# zigduino-micro-1.net
KiCad netlist of a schematic drawn in EAGLE
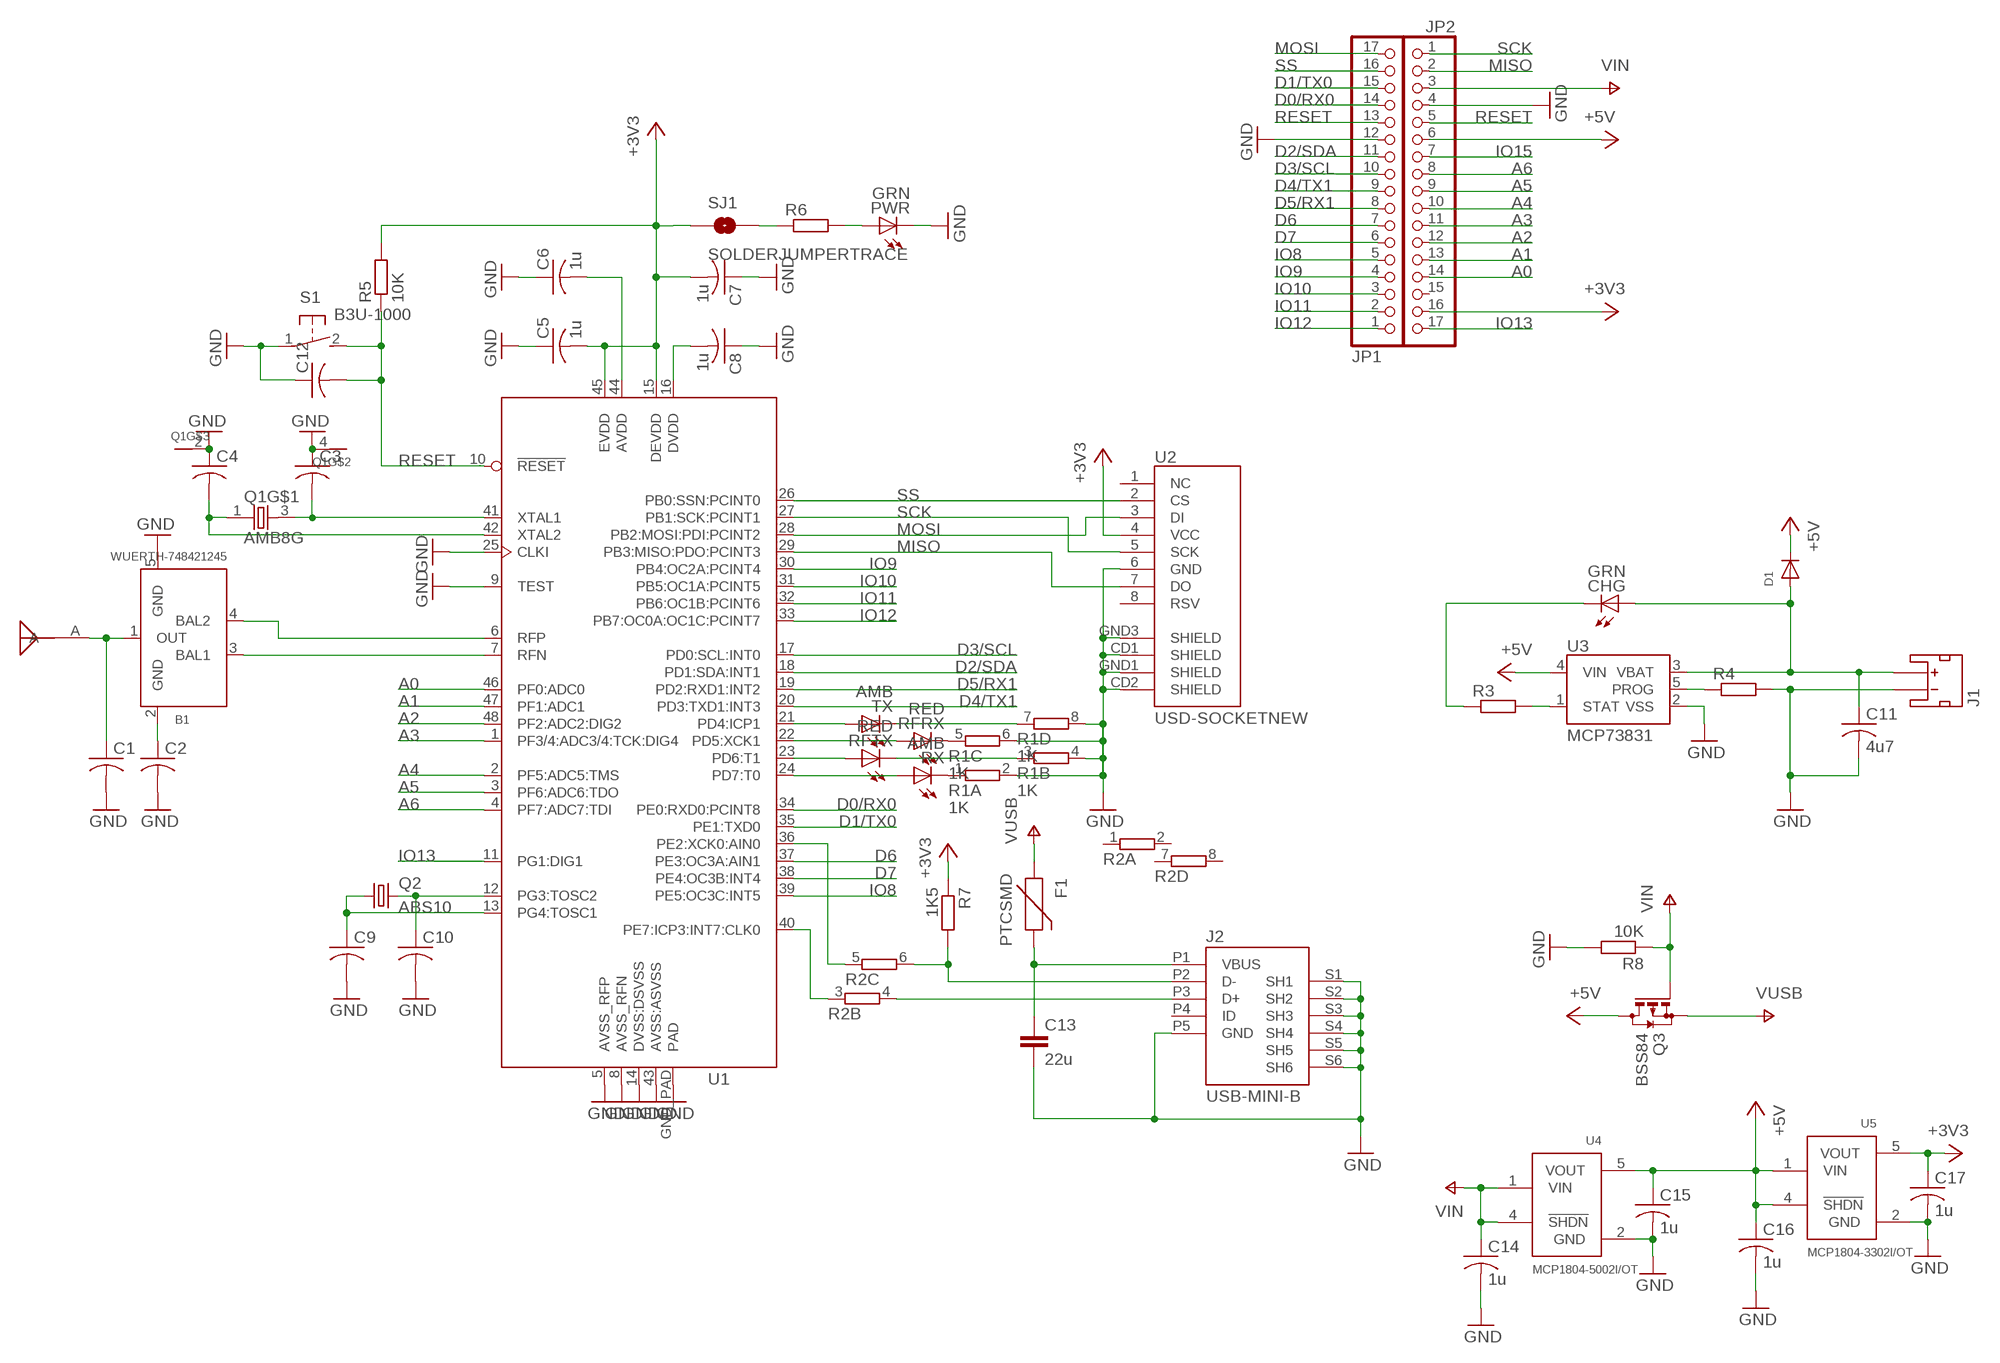
[diagram p0: schematic, sheet 1]

(export (version "E")
  (design (tool "Eeschema 10.0.6"))
  (components
    (comp (ref "ANT1")
      (value "ATMEGA128RFA1_MOLEX-ANT")
      (footprint "eagle-import:ATMEGA128RFA1_MOLEX-ANT")
      (libsource (lib "eagle-import") (part "ATMEGA128RFA1_MOLEX-ANT"))
    )
    (comp (ref "B1")
      (value "WUERTH-748421245")
      (footprint "eagle-import:WURTH-BALUN")
      (libsource (lib "eagle-import") (part "WUERTH-748421245"))
    )
    (comp (ref "C1")
      (value "C-USC0402")
      (footprint "eagle-import:C0402")
      (libsource (lib "eagle-import") (part "C-USC0402"))
    )
    (comp (ref "C2")
      (value "C-USC0402")
      (footprint "eagle-import:C0402")
      (libsource (lib "eagle-import") (part "C-USC0402"))
    )
    (comp (ref "C3")
      (value "C-USC0402")
      (footprint "eagle-import:C0402")
      (libsource (lib "eagle-import") (part "C-USC0402"))
    )
    (comp (ref "C4")
      (value "C-USC0402")
      (footprint "eagle-import:C0402")
      (libsource (lib "eagle-import") (part "C-USC0402"))
    )
    (comp (ref "C5")
      (value "1u")
      (footprint "eagle-import:C0402")
      (libsource (lib "eagle-import") (part "C-USC0402"))
    )
    (comp (ref "C6")
      (value "1u")
      (footprint "eagle-import:C0402")
      (libsource (lib "eagle-import") (part "C-USC0402"))
    )
    (comp (ref "C7")
      (value "1u")
      (footprint "eagle-import:C0402")
      (libsource (lib "eagle-import") (part "C-USC0402"))
    )
    (comp (ref "C8")
      (value "1u")
      (footprint "eagle-import:C0402")
      (libsource (lib "eagle-import") (part "C-USC0402"))
    )
    (comp (ref "C9")
      (value "C-USC0402")
      (footprint "eagle-import:C0402")
      (libsource (lib "eagle-import") (part "C-USC0402"))
    )
    (comp (ref "C10")
      (value "C-USC0402")
      (footprint "eagle-import:C0402")
      (libsource (lib "eagle-import") (part "C-USC0402"))
    )
    (comp (ref "C11")
      (value "4u7")
      (footprint "eagle-import:C0402")
      (libsource (lib "eagle-import") (part "C-USC0402"))
    )
    (comp (ref "C12")
      (value "C-USC0402")
      (footprint "eagle-import:C0402")
      (libsource (lib "eagle-import") (part "C-USC0402"))
    )
    (comp (ref "C13")
      (value "22u")
      (footprint "eagle-import:C0805")
      (libsource (lib "eagle-import") (part "C-EUC0805"))
    )
    (comp (ref "C14")
      (value "1u")
      (footprint "eagle-import:C0402")
      (libsource (lib "eagle-import") (part "C-USC0402"))
    )
    (comp (ref "C15")
      (value "1u")
      (footprint "eagle-import:C0402")
      (libsource (lib "eagle-import") (part "C-USC0402"))
    )
    (comp (ref "C16")
      (value "1u")
      (footprint "eagle-import:C0402")
      (libsource (lib "eagle-import") (part "C-USC0402"))
    )
    (comp (ref "C17")
      (value "1u")
      (footprint "eagle-import:C0402")
      (libsource (lib "eagle-import") (part "C-USC0402"))
    )
    (comp (ref "CHG")
      (value "GRN")
      (footprint "eagle-import:CHIPLED_0603")
      (libsource (lib "eagle-import") (part "LEDCHIPLED_0603"))
    )
    (comp (ref "D1")
      (value "DIODESOD-123")
      (footprint "eagle-import:SOD-123")
      (libsource (lib "eagle-import") (part "DIODESOD-123"))
    )
    (comp (ref "F1")
      (value "PTCSMD")
      (footprint "eagle-import:PTC-1206")
      (libsource (lib "eagle-import") (part "PTCSMD"))
    )
    (comp (ref "J1")
      (value "JST_2MM_MALE")
      (footprint "eagle-import:JST-2-SMD")
      (libsource (lib "eagle-import") (part "JST_2MM_MALE"))
    )
    (comp (ref "J2")
      (value "USB-MINI-B")
      (footprint "eagle-import:SMARTPRJ_CON2_USB_MICRO_B_AT")
      (libsource (lib "eagle-import") (part "USB-MINI-B"))
    )
    (comp (ref "JP1")
      (value "PINHD-1X17_2.54-SMD")
      (footprint "eagle-import:1X17SMD")
      (libsource (lib "eagle-import") (part "PINHD-1X17_2.54-SMD"))
    )
    (comp (ref "JP2")
      (value "PINHD-1X17_2.54-SMD")
      (footprint "eagle-import:1X17SMD")
      (libsource (lib "eagle-import") (part "PINHD-1X17_2.54-SMD"))
    )
    (comp (ref "PWR")
      (value "GRN")
      (footprint "eagle-import:CHIPLED_0603")
      (libsource (lib "eagle-import") (part "LEDCHIPLED_0603"))
    )
    (comp (ref "Q1")
      (value "AMB8G")
      (footprint "eagle-import:ABM8G")
      (libsource (lib "eagle-import") (part "AMB8G"))
    )
    (comp (ref "Q2")
      (value "ABS10")
      (footprint "eagle-import:ABS10")
      (libsource (lib "eagle-import") (part "ABS10"))
    )
    (comp (ref "Q3")
      (value "BSS84")
      (footprint "eagle-import:SOT23")
      (libsource (lib "eagle-import") (part "BSS84"))
    )
    (comp (ref "R1")
      (value "1K")
      (footprint "eagle-import:CTS742C083-RES")
      (libsource (lib "eagle-import") (part "4R-NCTS742C083"))
    )
    (comp (ref "R2")
      (value "4R-NCTS742C083")
      (footprint "eagle-import:CTS742C083-RES")
      (libsource (lib "eagle-import") (part "4R-NCTS742C083"))
    )
    (comp (ref "R3")
      (value "R-EU_R0402")
      (footprint "eagle-import:R0402")
      (libsource (lib "eagle-import") (part "R-EU_R0402"))
    )
    (comp (ref "R4")
      (value "R-EU_R0402")
      (footprint "eagle-import:R0402")
      (libsource (lib "eagle-import") (part "R-EU_R0402"))
    )
    (comp (ref "R5")
      (value "10K")
      (footprint "eagle-import:R0402")
      (libsource (lib "eagle-import") (part "R-EU_R0402"))
    )
    (comp (ref "R6")
      (value "R-EU_R0402")
      (footprint "eagle-import:R0402")
      (libsource (lib "eagle-import") (part "R-EU_R0402"))
    )
    (comp (ref "R7")
      (value "1K5")
      (footprint "eagle-import:R0402")
      (libsource (lib "eagle-import") (part "R-EU_R0402"))
    )
    (comp (ref "R8")
      (value "10K")
      (footprint "eagle-import:R0402")
      (libsource (lib "eagle-import") (part "R-EU_R0402"))
    )
    (comp (ref "RFRX")
      (value "RED")
      (footprint "eagle-import:CHIPLED_0603")
      (libsource (lib "eagle-import") (part "LEDCHIPLED_0603"))
    )
    (comp (ref "RFTX")
      (value "RED")
      (footprint "eagle-import:CHIPLED_0603")
      (libsource (lib "eagle-import") (part "LEDCHIPLED_0603"))
    )
    (comp (ref "RX")
      (value "AMB")
      (footprint "eagle-import:CHIPLED_0603")
      (libsource (lib "eagle-import") (part "LEDCHIPLED_0603"))
    )
    (comp (ref "S1")
      (value "B3U-1000")
      (footprint "eagle-import:B3U")
      (libsource (lib "eagle-import") (part "B3U-1000"))
    )
    (comp (ref "SJ1")
      (value "SOLDERJUMPERTRACE")
      (footprint "eagle-import:SJ_2S-TRACE")
      (libsource (lib "eagle-import") (part "SOLDERJUMPERTRACE"))
    )
    (comp (ref "TX")
      (value "AMB")
      (footprint "eagle-import:CHIPLED_0603")
      (libsource (lib "eagle-import") (part "LEDCHIPLED_0603"))
    )
    (comp (ref "U1")
      (value "ATMEGA1284RFR2")
      (footprint "eagle-import:QFN48")
      (libsource (lib "eagle-import") (part "ATMEGA1284RFR2"))
    )
    (comp (ref "U2")
      (value "USD-SOCKETNEW")
      (footprint "eagle-import:MICRO-SD-SOCKET-PP")
      (libsource (lib "eagle-import") (part "USD-SOCKETNEW"))
    )
    (comp (ref "U3")
      (value "MCP73831")
      (footprint "eagle-import:SOT23-5")
      (libsource (lib "eagle-import") (part "MCP73831"))
    )
    (comp (ref "U4")
      (value "MCP1804-5002I/OT")
      (footprint "eagle-import:SOT23-5L")
      (libsource (lib "eagle-import") (part "MCP1804-5002I/OT"))
    )
    (comp (ref "U5")
      (value "MCP1804-3302I/OT")
      (footprint "eagle-import:SOT23-5L")
      (libsource (lib "eagle-import") (part "MCP1804-3302I/OT"))
    )
  )
  (nets
    (net (code "1") (name "+3V3") (class "Default")
      (node (ref "C17") (pin "1") (pinfunction "1_1") (pintype "passive"))
      (node (ref "C5") (pin "2") (pinfunction "2_2") (pintype "passive"))
      (node (ref "C7") (pin "2") (pinfunction "2_2") (pintype "passive"))
      (node (ref "JP2") (pin "16") (pinfunction "16_16") (pintype "passive"))
      (node (ref "R5") (pin "2") (pinfunction "2_2") (pintype "passive"))
      (node (ref "R7") (pin "1") (pinfunction "1_1") (pintype "passive"))
      (node (ref "SJ1") (pin "1") (pinfunction "1_1") (pintype "passive"))
      (node (ref "U1") (pin "15") (pinfunction "DEVDD_15") (pintype "bidirectional"))
      (node (ref "U1") (pin "45") (pinfunction "EVDD_45") (pintype "bidirectional"))
      (node (ref "U2") (pin "4") (pinfunction "VCC_4") (pintype "bidirectional"))
      (node (ref "U5") (pin "5") (pinfunction "VOUT_5") (pintype "bidirectional"))
    )
    (net (code "2") (name "+5V") (class "Default")
      (node (ref "C15") (pin "1") (pinfunction "1_1") (pintype "passive"))
      (node (ref "C16") (pin "1") (pinfunction "1_1") (pintype "passive"))
      (node (ref "D1") (pin "C") (pinfunction "C_C") (pintype "passive"))
      (node (ref "JP2") (pin "6") (pinfunction "6_6") (pintype "passive"))
      (node (ref "Q3") (pin "3") (pinfunction "D_3") (pintype "passive"))
      (node (ref "U3") (pin "4") (pinfunction "VIN_4") (pintype "power_in"))
      (node (ref "U4") (pin "5") (pinfunction "VOUT_5") (pintype "bidirectional"))
      (node (ref "U5") (pin "1") (pinfunction "VIN_1") (pintype "bidirectional"))
      (node (ref "U5") (pin "4") (pinfunction "~{SHDN}_4") (pintype "bidirectional"))
    )
    (net (code "3") (name "/A0") (class "Default")
      (node (ref "JP2") (pin "14") (pinfunction "14_14") (pintype "passive"))
      (node (ref "U1") (pin "46") (pinfunction "PF0:ADC0_46") (pintype "bidirectional"))
    )
    (net (code "4") (name "/A1") (class "Default")
      (node (ref "JP2") (pin "13") (pinfunction "13_13") (pintype "passive"))
      (node (ref "U1") (pin "47") (pinfunction "PF1:ADC1_47") (pintype "bidirectional"))
    )
    (net (code "5") (name "/A2") (class "Default")
      (node (ref "JP2") (pin "12") (pinfunction "12_12") (pintype "passive"))
      (node (ref "U1") (pin "48") (pinfunction "PF2:ADC2:DIG2_48") (pintype "bidirectional"))
    )
    (net (code "6") (name "/A3") (class "Default")
      (node (ref "JP2") (pin "11") (pinfunction "11_11") (pintype "passive"))
      (node (ref "U1") (pin "1") (pinfunction "PF3/4:ADC3/4:TCK:DIG4_1") (pintype "bidirectional"))
    )
    (net (code "7") (name "/A4") (class "Default")
      (node (ref "JP2") (pin "10") (pinfunction "10_10") (pintype "passive"))
      (node (ref "U1") (pin "2") (pinfunction "PF5:ADC5:TMS_2") (pintype "bidirectional"))
    )
    (net (code "8") (name "/A5") (class "Default")
      (node (ref "JP2") (pin "9") (pinfunction "9_9") (pintype "passive"))
      (node (ref "U1") (pin "3") (pinfunction "PF6:ADC6:TDO_3") (pintype "bidirectional"))
    )
    (net (code "9") (name "/A6") (class "Default")
      (node (ref "JP2") (pin "8") (pinfunction "8_8") (pintype "passive"))
      (node (ref "U1") (pin "4") (pinfunction "PF7:ADC7:TDI_4") (pintype "bidirectional"))
    )
    (net (code "10") (name "/D0{slash}RX0") (class "Default")
      (node (ref "JP1") (pin "14") (pinfunction "14_14") (pintype "passive"))
      (node (ref "U1") (pin "34") (pinfunction "PE0:RXD0:PCINT8_34") (pintype "bidirectional"))
    )
    (net (code "11") (name "/D1{slash}TX0") (class "Default")
      (node (ref "JP1") (pin "15") (pinfunction "15_15") (pintype "passive"))
      (node (ref "U1") (pin "35") (pinfunction "PE1:TXD0_35") (pintype "bidirectional"))
    )
    (net (code "12") (name "/D2{slash}SDA") (class "Default")
      (node (ref "JP1") (pin "11") (pinfunction "11_11") (pintype "passive"))
      (node (ref "U1") (pin "18") (pinfunction "PD1:SDA:INT1_18") (pintype "bidirectional"))
    )
    (net (code "13") (name "/D3{slash}SCL") (class "Default")
      (node (ref "JP1") (pin "10") (pinfunction "10_10") (pintype "passive"))
      (node (ref "U1") (pin "17") (pinfunction "PD0:SCL:INT0_17") (pintype "bidirectional"))
    )
    (net (code "14") (name "/D4{slash}TX1") (class "Default")
      (node (ref "JP1") (pin "9") (pinfunction "9_9") (pintype "passive"))
      (node (ref "U1") (pin "20") (pinfunction "PD3:TXD1:INT3_20") (pintype "bidirectional"))
    )
    (net (code "15") (name "/D5{slash}RX1") (class "Default")
      (node (ref "JP1") (pin "8") (pinfunction "8_8") (pintype "passive"))
      (node (ref "U1") (pin "19") (pinfunction "PD2:RXD1:INT2_19") (pintype "bidirectional"))
    )
    (net (code "16") (name "/D6") (class "Default")
      (node (ref "JP1") (pin "7") (pinfunction "7_7") (pintype "passive"))
      (node (ref "U1") (pin "37") (pinfunction "PE3:OC3A:AIN1_37") (pintype "bidirectional"))
    )
    (net (code "17") (name "/D7") (class "Default")
      (node (ref "JP1") (pin "6") (pinfunction "6_6") (pintype "passive"))
      (node (ref "U1") (pin "38") (pinfunction "PE4:OC3B:INT4_38") (pintype "bidirectional"))
    )
    (net (code "18") (name "/IO8") (class "Default")
      (node (ref "JP1") (pin "5") (pinfunction "5_5") (pintype "passive"))
      (node (ref "U1") (pin "39") (pinfunction "PE5:OC3C:INT5_39") (pintype "bidirectional"))
    )
    (net (code "19") (name "/IO9") (class "Default")
      (node (ref "JP1") (pin "4") (pinfunction "4_4") (pintype "passive"))
      (node (ref "U1") (pin "30") (pinfunction "PB4:OC2A:PCINT4_30") (pintype "bidirectional"))
    )
    (net (code "20") (name "/IO10") (class "Default")
      (node (ref "JP1") (pin "3") (pinfunction "3_3") (pintype "passive"))
      (node (ref "U1") (pin "31") (pinfunction "PB5:OC1A:PCINT5_31") (pintype "bidirectional"))
    )
    (net (code "21") (name "/IO11") (class "Default")
      (node (ref "JP1") (pin "2") (pinfunction "2_2") (pintype "passive"))
      (node (ref "U1") (pin "32") (pinfunction "PB6:OC1B:PCINT6_32") (pintype "bidirectional"))
    )
    (net (code "22") (name "/IO12") (class "Default")
      (node (ref "JP1") (pin "1") (pinfunction "1_1") (pintype "passive"))
      (node (ref "U1") (pin "33") (pinfunction "PB7:OC0A:OC1C:PCINT7_33") (pintype "bidirectional"))
    )
    (net (code "23") (name "/IO13") (class "Default")
      (node (ref "JP2") (pin "17") (pinfunction "17_17") (pintype "passive"))
      (node (ref "U1") (pin "11") (pinfunction "PG1:DIG1_11") (pintype "bidirectional"))
    )
    (net (code "24") (name "/IO15") (class "Default")
      (node (ref "JP2") (pin "7") (pinfunction "7_7") (pintype "passive"))
    )
    (net (code "25") (name "/MISO") (class "Default")
      (node (ref "JP2") (pin "2") (pinfunction "2_2") (pintype "passive"))
      (node (ref "U1") (pin "29") (pinfunction "PB3:MISO:PDO:PCINT3_29") (pintype "bidirectional"))
      (node (ref "U2") (pin "7") (pinfunction "DO_7") (pintype "bidirectional"))
    )
    (net (code "26") (name "/MOSI") (class "Default")
      (node (ref "JP1") (pin "17") (pinfunction "17_17") (pintype "passive"))
      (node (ref "U1") (pin "28") (pinfunction "PB2:MOSI:PDI:PCINT2_28") (pintype "bidirectional"))
      (node (ref "U2") (pin "3") (pinfunction "DI_3") (pintype "bidirectional"))
    )
    (net (code "27") (name "/RESET") (class "Default")
      (node (ref "C12") (pin "2") (pinfunction "2_2") (pintype "passive"))
      (node (ref "JP1") (pin "13") (pinfunction "13_13") (pintype "passive"))
      (node (ref "JP2") (pin "5") (pinfunction "5_5") (pintype "passive"))
      (node (ref "R5") (pin "1") (pinfunction "1_1") (pintype "passive"))
      (node (ref "S1") (pin "2") (pinfunction "2_2") (pintype "passive"))
      (node (ref "U1") (pin "10") (pinfunction "~{RESET}_10") (pintype "bidirectional"))
    )
    (net (code "28") (name "/SCK") (class "Default")
      (node (ref "JP2") (pin "1") (pinfunction "1_1") (pintype "passive"))
      (node (ref "U1") (pin "27") (pinfunction "PB1:SCK:PCINT1_27") (pintype "bidirectional"))
      (node (ref "U2") (pin "5") (pinfunction "SCK_5") (pintype "bidirectional"))
    )
    (net (code "29") (name "/SS") (class "Default")
      (node (ref "JP1") (pin "16") (pinfunction "16_16") (pintype "passive"))
      (node (ref "U1") (pin "26") (pinfunction "PB0:SSN:PCINT0_26") (pintype "bidirectional"))
      (node (ref "U2") (pin "2") (pinfunction "CS_2") (pintype "bidirectional"))
    )
    (net (code "30") (name "GND") (class "Default")
      (node (ref "B1") (pin "5") (pinfunction "GND_5") (pintype "bidirectional"))
      (node (ref "C1") (pin "2") (pinfunction "2_2") (pintype "passive"))
      (node (ref "C10") (pin "2") (pinfunction "2_2") (pintype "passive"))
      (node (ref "C11") (pin "2") (pinfunction "2_2") (pintype "passive"))
      (node (ref "C12") (pin "1") (pinfunction "1_1") (pintype "passive"))
      (node (ref "C13") (pin "2") (pinfunction "2_2") (pintype "passive"))
      (node (ref "C14") (pin "2") (pinfunction "2_2") (pintype "passive"))
      (node (ref "C15") (pin "2") (pinfunction "2_2") (pintype "passive"))
      (node (ref "C16") (pin "2") (pinfunction "2_2") (pintype "passive"))
      (node (ref "C17") (pin "2") (pinfunction "2_2") (pintype "passive"))
      (node (ref "C2") (pin "2") (pinfunction "2_2") (pintype "passive"))
      (node (ref "C3") (pin "1") (pinfunction "1_1") (pintype "passive"))
      (node (ref "C4") (pin "1") (pinfunction "1_1") (pintype "passive"))
      (node (ref "C5") (pin "1") (pinfunction "1_1") (pintype "passive"))
      (node (ref "C6") (pin "1") (pinfunction "1_1") (pintype "passive"))
      (node (ref "C7") (pin "1") (pinfunction "1_1") (pintype "passive"))
      (node (ref "C8") (pin "1") (pinfunction "1_1") (pintype "passive"))
      (node (ref "C9") (pin "2") (pinfunction "2_2") (pintype "passive"))
      (node (ref "J1") (pin "1") (pinfunction "-_1") (pintype "bidirectional"))
      (node (ref "J2") (pin "P5") (pinfunction "GND_P5") (pintype "passive"))
      (node (ref "J2") (pin "S1") (pinfunction "SH1_S1") (pintype "passive"))
      (node (ref "J2") (pin "S2") (pinfunction "SH2_S2") (pintype "passive"))
      (node (ref "J2") (pin "S3") (pinfunction "SH3_S3") (pintype "passive"))
      (node (ref "J2") (pin "S4") (pinfunction "SH4_S4") (pintype "passive"))
      (node (ref "J2") (pin "S5") (pinfunction "SH5_S5") (pintype "passive"))
      (node (ref "J2") (pin "S6") (pinfunction "SH6_S6") (pintype "passive"))
      (node (ref "JP1") (pin "12") (pinfunction "12_12") (pintype "passive"))
      (node (ref "JP2") (pin "4") (pinfunction "4_4") (pintype "passive"))
      (node (ref "PWR") (pin "C") (pinfunction "C_C") (pintype "passive"))
      (node (ref "Q1") (pin "2") (pinfunction "PIN_2") (pintype "bidirectional"))
      (node (ref "Q1") (pin "4") (pinfunction "PIN_4") (pintype "bidirectional"))
      (node (ref "R1") (pin "2") (pinfunction "2_2") (pintype "passive"))
      (node (ref "R1") (pin "4") (pinfunction "2_4") (pintype "passive"))
      (node (ref "R1") (pin "6") (pinfunction "2_6") (pintype "passive"))
      (node (ref "R1") (pin "8") (pinfunction "2_8") (pintype "passive"))
      (node (ref "R4") (pin "2") (pinfunction "2_2") (pintype "passive"))
      (node (ref "R8") (pin "2") (pinfunction "2_2") (pintype "passive"))
      (node (ref "S1") (pin "1") (pinfunction "1_1") (pintype "passive"))
      (node (ref "U1") (pin "14") (pinfunction "DVSS:DSVSS_14") (pintype "bidirectional"))
      (node (ref "U1") (pin "25") (pinfunction "CLKI_25") (pintype "bidirectional"))
      (node (ref "U1") (pin "43") (pinfunction "AVSS:ASVSS_43") (pintype "bidirectional"))
      (node (ref "U1") (pin "5") (pinfunction "AVSS_RFP_5") (pintype "bidirectional"))
      (node (ref "U1") (pin "8") (pinfunction "AVSS_RFN_8") (pintype "bidirectional"))
      (node (ref "U1") (pin "9") (pinfunction "TEST_9") (pintype "bidirectional"))
      (node (ref "U1") (pin "GND_PAD") (pinfunction "PAD_GND_PAD") (pintype "bidirectional"))
      (node (ref "U2") (pin "6") (pinfunction "GND_6") (pintype "bidirectional"))
      (node (ref "U2") (pin "CD1") (pinfunction "SHIELD_CD1") (pintype "bidirectional"))
      (node (ref "U2") (pin "CD2") (pinfunction "SHIELD_CD2") (pintype "bidirectional"))
      (node (ref "U2") (pin "GND1") (pinfunction "SHIELD_GND1") (pintype "bidirectional"))
      (node (ref "U2") (pin "GND3") (pinfunction "SHIELD_GND3") (pintype "bidirectional"))
      (node (ref "U3") (pin "2") (pinfunction "VSS_2") (pintype "power_in"))
      (node (ref "U4") (pin "2") (pinfunction "GND_2") (pintype "bidirectional"))
      (node (ref "U5") (pin "2") (pinfunction "GND_2") (pintype "bidirectional"))
    )
    (net (code "31") (name "Net-(B1-BAL1)") (class "Default")
      (node (ref "B1") (pin "3") (pinfunction "BAL1_3") (pintype "bidirectional"))
      (node (ref "U1") (pin "7") (pinfunction "RFN_7") (pintype "bidirectional"))
    )
    (net (code "32") (name "Net-(B1-BAL2)") (class "Default")
      (node (ref "B1") (pin "4") (pinfunction "BAL2_4") (pintype "bidirectional"))
      (node (ref "U1") (pin "6") (pinfunction "RFP_6") (pintype "bidirectional"))
    )
    (net (code "33") (name "Net-(B1-GND-Pad2)") (class "Default")
      (node (ref "B1") (pin "2") (pinfunction "GND_2") (pintype "bidirectional"))
      (node (ref "C2") (pin "1") (pinfunction "1_1") (pintype "passive"))
    )
    (net (code "34") (name "Net-(B1-OUT)") (class "Default")
      (node (ref "ANT1") (pin "A") (pinfunction "A_A") (pintype "bidirectional"))
      (node (ref "B1") (pin "1") (pinfunction "OUT_1") (pintype "bidirectional"))
      (node (ref "C1") (pin "1") (pinfunction "1_1") (pintype "passive"))
    )
    (net (code "35") (name "Net-(CHG-PadC)") (class "Default")
      (node (ref "CHG") (pin "C") (pinfunction "C_C") (pintype "passive"))
      (node (ref "R3") (pin "1") (pinfunction "1_1") (pintype "passive"))
    )
    (net (code "36") (name "Net-(J1-+)") (class "Default")
      (node (ref "C11") (pin "1") (pinfunction "1_1") (pintype "passive"))
      (node (ref "CHG") (pin "A") (pinfunction "A_A") (pintype "passive"))
      (node (ref "D1") (pin "A") (pinfunction "A_A") (pintype "passive"))
      (node (ref "J1") (pin "2") (pinfunction "+_2") (pintype "bidirectional"))
      (node (ref "U3") (pin "3") (pinfunction "VBAT_3") (pintype "power_in"))
    )
    (net (code "37") (name "Net-(J2-D+)") (class "Default")
      (node (ref "J2") (pin "P3") (pinfunction "D+_P3") (pintype "bidirectional"))
      (node (ref "R2") (pin "4") (pinfunction "2_4") (pintype "passive"))
    )
    (net (code "38") (name "Net-(J2-D-)") (class "Default")
      (node (ref "J2") (pin "P2") (pinfunction "D-_P2") (pintype "bidirectional"))
      (node (ref "R2") (pin "6") (pinfunction "2_6") (pintype "passive"))
      (node (ref "R7") (pin "2") (pinfunction "2_2") (pintype "passive"))
    )
    (net (code "39") (name "Net-(J2-VBUS)") (class "Default")
      (node (ref "C13") (pin "1") (pinfunction "1_1") (pintype "passive"))
      (node (ref "F1") (pin "2") (pinfunction "2_2") (pintype "bidirectional"))
      (node (ref "J2") (pin "P1") (pinfunction "VBUS_P1") (pintype "power_in"))
    )
    (net (code "40") (name "Net-(PWR-PadA)") (class "Default")
      (node (ref "PWR") (pin "A") (pinfunction "A_A") (pintype "passive"))
      (node (ref "R6") (pin "2") (pinfunction "2_2") (pintype "passive"))
    )
    (net (code "41") (name "Net-(Q1A-2)") (class "Default")
      (node (ref "C3") (pin "2") (pinfunction "2_2") (pintype "passive"))
      (node (ref "Q1") (pin "3") (pinfunction "2_3") (pintype "passive"))
      (node (ref "U1") (pin "41") (pinfunction "XTAL1_41") (pintype "bidirectional"))
    )
    (net (code "42") (name "Net-(R1-Pad1)") (class "Default")
      (node (ref "R1") (pin "1") (pinfunction "1_1") (pintype "passive"))
      (node (ref "RX") (pin "C") (pinfunction "C_C") (pintype "passive"))
    )
    (net (code "43") (name "Net-(R1B-1)") (class "Default")
      (node (ref "R1") (pin "3") (pinfunction "1_3") (pintype "passive"))
      (node (ref "RFTX") (pin "C") (pinfunction "C_C") (pintype "passive"))
    )
    (net (code "44") (name "Net-(R1C-1)") (class "Default")
      (node (ref "R1") (pin "5") (pinfunction "1_5") (pintype "passive"))
      (node (ref "RFRX") (pin "C") (pinfunction "C_C") (pintype "passive"))
    )
    (net (code "45") (name "Net-(R1D-1)") (class "Default")
      (node (ref "R1") (pin "7") (pinfunction "1_7") (pintype "passive"))
      (node (ref "TX") (pin "C") (pinfunction "C_C") (pintype "passive"))
    )
    (net (code "46") (name "Net-(R2B-1)") (class "Default")
      (node (ref "R2") (pin "3") (pinfunction "1_3") (pintype "passive"))
      (node (ref "U1") (pin "40") (pinfunction "PE7:ICP3:INT7:CLK0_40") (pintype "bidirectional"))
    )
    (net (code "47") (name "Net-(R2C-1)") (class "Default")
      (node (ref "R2") (pin "5") (pinfunction "1_5") (pintype "passive"))
      (node (ref "U1") (pin "36") (pinfunction "PE2:XCK0:AIN0_36") (pintype "bidirectional"))
    )
    (net (code "48") (name "Net-(R6-Pad1)") (class "Default")
      (node (ref "R6") (pin "1") (pinfunction "1_1") (pintype "passive"))
      (node (ref "SJ1") (pin "2") (pinfunction "2_2") (pintype "passive"))
    )
    (net (code "49") (name "Net-(U1-AVDD)") (class "Default")
      (node (ref "C6") (pin "2") (pinfunction "2_2") (pintype "passive"))
      (node (ref "U1") (pin "44") (pinfunction "AVDD_44") (pintype "bidirectional"))
    )
    (net (code "50") (name "Net-(U1-DVDD)") (class "Default")
      (node (ref "C8") (pin "2") (pinfunction "2_2") (pintype "passive"))
      (node (ref "U1") (pin "16") (pinfunction "DVDD_16") (pintype "bidirectional"))
    )
    (net (code "51") (name "Net-(U1-PD4:ICP1)") (class "Default")
      (node (ref "TX") (pin "A") (pinfunction "A_A") (pintype "passive"))
      (node (ref "U1") (pin "21") (pinfunction "PD4:ICP1_21") (pintype "bidirectional"))
    )
    (net (code "52") (name "Net-(U1-PD5:XCK1)") (class "Default")
      (node (ref "RFRX") (pin "A") (pinfunction "A_A") (pintype "passive"))
      (node (ref "U1") (pin "22") (pinfunction "PD5:XCK1_22") (pintype "bidirectional"))
    )
    (net (code "53") (name "Net-(U1-PD6:T1)") (class "Default")
      (node (ref "RFTX") (pin "A") (pinfunction "A_A") (pintype "passive"))
      (node (ref "U1") (pin "23") (pinfunction "PD6:T1_23") (pintype "bidirectional"))
    )
    (net (code "54") (name "Net-(U1-PD7:T0)") (class "Default")
      (node (ref "RX") (pin "A") (pinfunction "A_A") (pintype "passive"))
      (node (ref "U1") (pin "24") (pinfunction "PD7:T0_24") (pintype "bidirectional"))
    )
    (net (code "55") (name "Net-(U1-PG3:TOSC2)") (class "Default")
      (node (ref "C10") (pin "1") (pinfunction "1_1") (pintype "passive"))
      (node (ref "Q2") (pin "2") (pinfunction "2_2") (pintype "passive"))
      (node (ref "U1") (pin "12") (pinfunction "PG3:TOSC2_12") (pintype "bidirectional"))
    )
    (net (code "56") (name "Net-(U1-PG4:TOSC1)") (class "Default")
      (node (ref "C9") (pin "1") (pinfunction "1_1") (pintype "passive"))
      (node (ref "Q2") (pin "1") (pinfunction "1_1") (pintype "passive"))
      (node (ref "U1") (pin "13") (pinfunction "PG4:TOSC1_13") (pintype "bidirectional"))
    )
    (net (code "57") (name "Net-(U1-XTAL2)") (class "Default")
      (node (ref "C4") (pin "2") (pinfunction "2_2") (pintype "passive"))
      (node (ref "Q1") (pin "1") (pinfunction "1_1") (pintype "passive"))
      (node (ref "U1") (pin "42") (pinfunction "XTAL2_42") (pintype "bidirectional"))
    )
    (net (code "58") (name "Net-(U3-PROG)") (class "Default")
      (node (ref "R4") (pin "1") (pinfunction "1_1") (pintype "passive"))
      (node (ref "U3") (pin "5") (pinfunction "PROG_5") (pintype "input"))
    )
    (net (code "59") (name "Net-(U3-STAT)") (class "Default")
      (node (ref "R3") (pin "2") (pinfunction "2_2") (pintype "passive"))
      (node (ref "U3") (pin "1") (pinfunction "STAT_1") (pintype "output"))
    )
    (net (code "60") (name "VIN") (class "Default")
      (node (ref "C14") (pin "1") (pinfunction "1_1") (pintype "passive"))
      (node (ref "JP2") (pin "3") (pinfunction "3_3") (pintype "passive"))
      (node (ref "Q3") (pin "1") (pinfunction "G_1") (pintype "passive"))
      (node (ref "R8") (pin "1") (pinfunction "1_1") (pintype "passive"))
      (node (ref "U4") (pin "1") (pinfunction "VIN_1") (pintype "bidirectional"))
      (node (ref "U4") (pin "4") (pinfunction "~{SHDN}_4") (pintype "bidirectional"))
    )
    (net (code "61") (name "VUSB") (class "Default")
      (node (ref "F1") (pin "1") (pinfunction "1_1") (pintype "bidirectional"))
      (node (ref "Q3") (pin "2") (pinfunction "S_2") (pintype "passive"))
    )
    (net (code "62") (name "unconnected-(J1-PAD1-PadNC1)") (class "Default")
      (node (ref "J1") (pin "NC1") (pinfunction "PAD1_NC1") (pintype "bidirectional"))
    )
    (net (code "63") (name "unconnected-(J1-PAD2-PadNC2)") (class "Default")
      (node (ref "J1") (pin "NC2") (pinfunction "PAD2_NC2") (pintype "bidirectional"))
    )
    (net (code "64") (name "unconnected-(J2-ID-PadP4)") (class "Default")
      (node (ref "J2") (pin "P4") (pinfunction "ID_P4") (pintype "bidirectional"))
    )
    (net (code "65") (name "unconnected-(JP2-Pad15)") (class "Default")
      (node (ref "JP2") (pin "15") (pinfunction "15_15") (pintype "passive"))
    )
    (net (code "66") (name "unconnected-(R2-Pad1)") (class "Default")
      (node (ref "R2") (pin "1") (pinfunction "1_1") (pintype "passive"))
    )
    (net (code "67") (name "unconnected-(R2-Pad2)") (class "Default")
      (node (ref "R2") (pin "2") (pinfunction "2_2") (pintype "passive"))
    )
    (net (code "68") (name "unconnected-(R2D-1-Pad7)") (class "Default")
      (node (ref "R2") (pin "7") (pinfunction "1_7") (pintype "passive"))
    )
    (net (code "69") (name "unconnected-(R2D-2-Pad8)") (class "Default")
      (node (ref "R2") (pin "8") (pinfunction "2_8") (pintype "passive"))
    )
    (net (code "70") (name "unconnected-(U2-NC-Pad1)") (class "Default")
      (node (ref "U2") (pin "1") (pinfunction "NC_1") (pintype "bidirectional"))
    )
    (net (code "71") (name "unconnected-(U2-RSV-Pad8)") (class "Default")
      (node (ref "U2") (pin "8") (pinfunction "RSV_8") (pintype "bidirectional"))
    )
  )
)
